# A604E.net
KiCad netlist of a schematic drawn in EAGLE
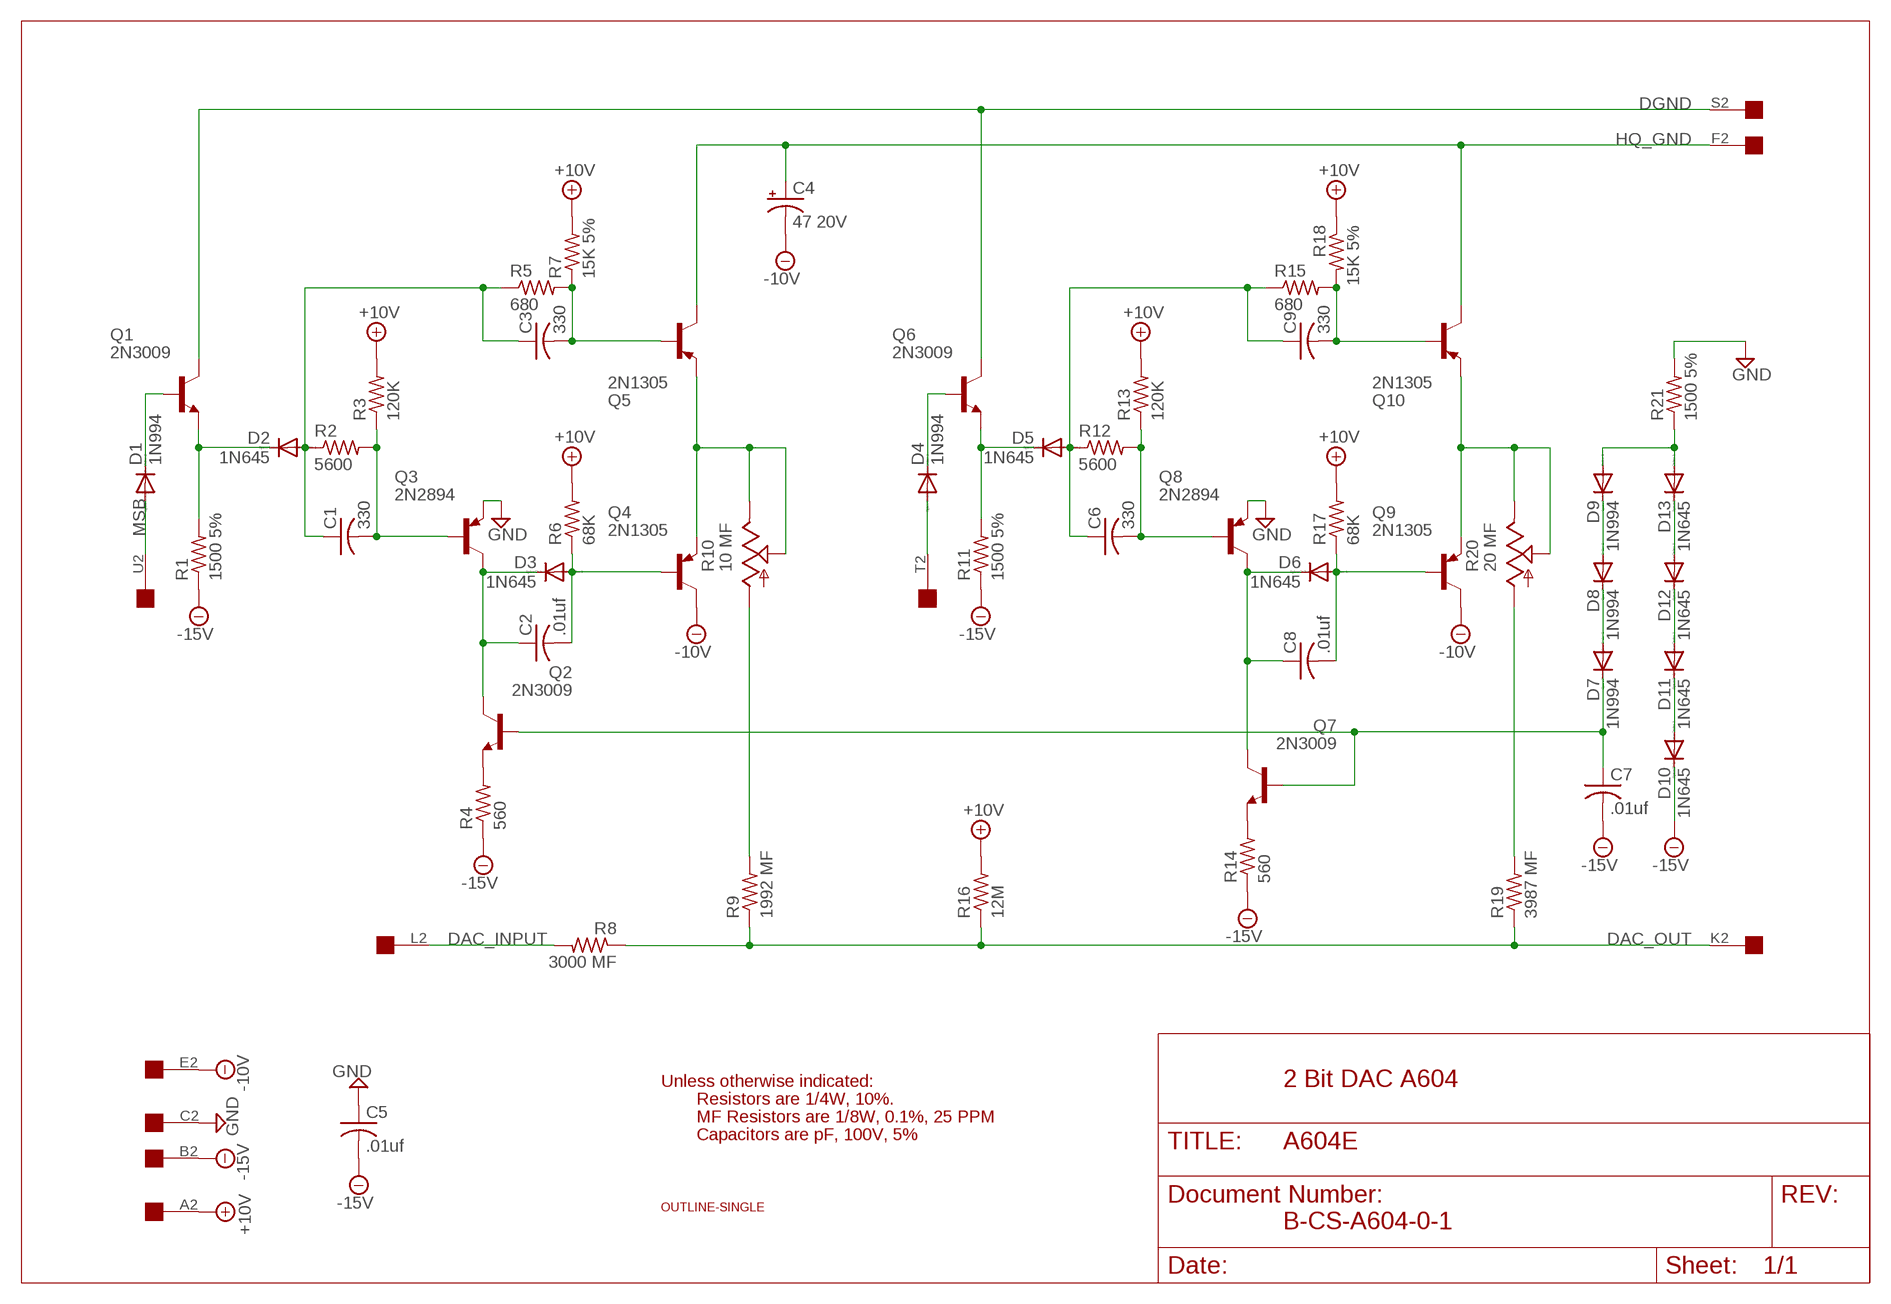
[diagram p0: schematic, sheet 1]

(export (version "E")
  (design (tool "Eeschema 10.0.6"))
  (components
    (comp (ref "C1")
      (value "330")
      (footprint "eagle-import:C075-032X103")
      (libsource (lib "eagle-import") (part "C-US075-032X103"))
    )
    (comp (ref "C2")
      (value ".01uf")
      (footprint "eagle-import:C050-025X075")
      (libsource (lib "eagle-import") (part "C-US050-025X075"))
    )
    (comp (ref "C3")
      (value "330")
      (footprint "eagle-import:C075-032X103")
      (libsource (lib "eagle-import") (part "C-US075-032X103"))
    )
    (comp (ref "C4")
      (value "47 20V")
      (footprint "eagle-import:E22-6")
      (libsource (lib "eagle-import") (part "CPOL-USE22-6AXIAL"))
    )
    (comp (ref "C5")
      (value ".01uf")
      (footprint "eagle-import:C050-025X075")
      (libsource (lib "eagle-import") (part "C-US050-025X075"))
    )
    (comp (ref "C6")
      (value "330")
      (footprint "eagle-import:C075-032X103")
      (libsource (lib "eagle-import") (part "C-US075-032X103"))
    )
    (comp (ref "C7")
      (value ".01uf")
      (footprint "eagle-import:C050-025X075")
      (libsource (lib "eagle-import") (part "C-US050-025X075"))
    )
    (comp (ref "C8")
      (value ".01uf")
      (footprint "eagle-import:C050-025X075")
      (libsource (lib "eagle-import") (part "C-US050-025X075"))
    )
    (comp (ref "C9")
      (value "330")
      (footprint "eagle-import:C075-032X103")
      (libsource (lib "eagle-import") (part "C-US075-032X103"))
    )
    (comp (ref "D1")
      (value "1N994")
      (footprint "eagle-import:DO35-10")
      (libsource (lib "eagle-import") (part "1N4148DO35-10"))
    )
    (comp (ref "D2")
      (value "1N645")
      (footprint "eagle-import:DO35-10")
      (libsource (lib "eagle-import") (part "1N4148DO35-10"))
    )
    (comp (ref "D3")
      (value "1N645")
      (footprint "eagle-import:DO35-10")
      (libsource (lib "eagle-import") (part "1N4148DO35-10"))
    )
    (comp (ref "D4")
      (value "1N994")
      (footprint "eagle-import:DO35-10")
      (libsource (lib "eagle-import") (part "1N4148DO35-10"))
    )
    (comp (ref "D5")
      (value "1N645")
      (footprint "eagle-import:DO35-10")
      (libsource (lib "eagle-import") (part "1N4148DO35-10"))
    )
    (comp (ref "D6")
      (value "1N645")
      (footprint "eagle-import:DO35-10")
      (libsource (lib "eagle-import") (part "1N4148DO35-10"))
    )
    (comp (ref "D7")
      (value "1N994")
      (footprint "eagle-import:DO35-10")
      (libsource (lib "eagle-import") (part "1N4148DO35-10"))
    )
    (comp (ref "D8")
      (value "1N994")
      (footprint "eagle-import:DO35-10")
      (libsource (lib "eagle-import") (part "1N4148DO35-10"))
    )
    (comp (ref "D9")
      (value "1N994")
      (footprint "eagle-import:DO35-10")
      (libsource (lib "eagle-import") (part "1N4148DO35-10"))
    )
    (comp (ref "D10")
      (value "1N645")
      (footprint "eagle-import:DO35-10")
      (libsource (lib "eagle-import") (part "1N4148DO35-10"))
    )
    (comp (ref "D11")
      (value "1N645")
      (footprint "eagle-import:DO35-10")
      (libsource (lib "eagle-import") (part "1N4148DO35-10"))
    )
    (comp (ref "D12")
      (value "1N645")
      (footprint "eagle-import:DO35-10")
      (libsource (lib "eagle-import") (part "1N4148DO35-10"))
    )
    (comp (ref "D13")
      (value "1N645")
      (footprint "eagle-import:DO35-10")
      (libsource (lib "eagle-import") (part "1N4148DO35-10"))
    )
    (comp (ref "Q1")
      (value "2N3009")
      (footprint "eagle-import:TO39")
      (libsource (lib "eagle-import") (part "-NPN-TO39-EBC2N1613"))
    )
    (comp (ref "Q2")
      (value "2N3009")
      (footprint "eagle-import:TO39")
      (libsource (lib "eagle-import") (part "-NPN-TO39-EBC2N1613"))
    )
    (comp (ref "Q3")
      (value "2N2894")
      (footprint "eagle-import:TO39")
      (libsource (lib "eagle-import") (part "2N2904A"))
    )
    (comp (ref "Q4")
      (value "2N1305")
      (footprint "eagle-import:TO39")
      (libsource (lib "eagle-import") (part "2N2904A"))
    )
    (comp (ref "Q5")
      (value "2N1305")
      (footprint "eagle-import:TO39")
      (libsource (lib "eagle-import") (part "2N2904A"))
    )
    (comp (ref "Q6")
      (value "2N3009")
      (footprint "eagle-import:TO39")
      (libsource (lib "eagle-import") (part "-NPN-TO39-EBC2N1613"))
    )
    (comp (ref "Q7")
      (value "2N3009")
      (footprint "eagle-import:TO39")
      (libsource (lib "eagle-import") (part "-NPN-TO39-EBC2N1613"))
    )
    (comp (ref "Q8")
      (value "2N2894")
      (footprint "eagle-import:TO39")
      (libsource (lib "eagle-import") (part "2N2904A"))
    )
    (comp (ref "Q9")
      (value "2N1305")
      (footprint "eagle-import:TO39")
      (libsource (lib "eagle-import") (part "2N2904A"))
    )
    (comp (ref "Q10")
      (value "2N1305")
      (footprint "eagle-import:TO39")
      (libsource (lib "eagle-import") (part "2N2904A"))
    )
    (comp (ref "R1")
      (value "1500 5%")
      (footprint "eagle-import:0207_10")
      (libsource (lib "eagle-import") (part "R-US_0207/10"))
    )
    (comp (ref "R2")
      (value "5600")
      (footprint "eagle-import:0207_10")
      (libsource (lib "eagle-import") (part "R-US_0207/10"))
    )
    (comp (ref "R3")
      (value "120K")
      (footprint "eagle-import:0207_10")
      (libsource (lib "eagle-import") (part "R-US_0207/10"))
    )
    (comp (ref "R4")
      (value "560")
      (footprint "eagle-import:0207_10")
      (libsource (lib "eagle-import") (part "R-US_0207/10"))
    )
    (comp (ref "R5")
      (value "680")
      (footprint "eagle-import:0207_10")
      (libsource (lib "eagle-import") (part "R-US_0207/10"))
    )
    (comp (ref "R6")
      (value "68K")
      (footprint "eagle-import:0207_10")
      (libsource (lib "eagle-import") (part "R-US_0207/10"))
    )
    (comp (ref "R7")
      (value "15K 5%")
      (footprint "eagle-import:0207_10")
      (libsource (lib "eagle-import") (part "R-US_0207/10"))
    )
    (comp (ref "R8")
      (value "3000 MF")
      (footprint "eagle-import:0309_12")
      (libsource (lib "eagle-import") (part "R-US_0309/12"))
    )
    (comp (ref "R9")
      (value "1992 MF")
      (footprint "eagle-import:0309_12")
      (libsource (lib "eagle-import") (part "R-US_0309/12"))
    )
    (comp (ref "R10")
      (value "10 MF")
      (footprint "eagle-import:S75P")
      (libsource (lib "eagle-import") (part "TRIM_US-S75P"))
    )
    (comp (ref "R11")
      (value "1500 5%")
      (footprint "eagle-import:0207_10")
      (libsource (lib "eagle-import") (part "R-US_0207/10"))
    )
    (comp (ref "R12")
      (value "5600")
      (footprint "eagle-import:0207_10")
      (libsource (lib "eagle-import") (part "R-US_0207/10"))
    )
    (comp (ref "R13")
      (value "120K")
      (footprint "eagle-import:0207_10")
      (libsource (lib "eagle-import") (part "R-US_0207/10"))
    )
    (comp (ref "R14")
      (value "560")
      (footprint "eagle-import:0207_10")
      (libsource (lib "eagle-import") (part "R-US_0207/10"))
    )
    (comp (ref "R15")
      (value "680")
      (footprint "eagle-import:0207_10")
      (libsource (lib "eagle-import") (part "R-US_0207/10"))
    )
    (comp (ref "R16")
      (value "12M")
      (footprint "eagle-import:0207_10")
      (libsource (lib "eagle-import") (part "R-US_0207/10"))
    )
    (comp (ref "R17")
      (value "68K")
      (footprint "eagle-import:0207_10")
      (libsource (lib "eagle-import") (part "R-US_0207/10"))
    )
    (comp (ref "R18")
      (value "15K 5%")
      (footprint "eagle-import:0207_10")
      (libsource (lib "eagle-import") (part "R-US_0207/10"))
    )
    (comp (ref "R19")
      (value "3987 MF")
      (footprint "eagle-import:0309_12")
      (libsource (lib "eagle-import") (part "R-US_0309/12"))
    )
    (comp (ref "R20")
      (value "20 MF")
      (footprint "eagle-import:S75P")
      (libsource (lib "eagle-import") (part "TRIM_US-S75P"))
    )
    (comp (ref "R21")
      (value "1500 5%")
      (footprint "eagle-import:0207_10")
      (libsource (lib "eagle-import") (part "R-US_0207/10"))
    )
    (comp (ref "U$1")
      (value "OUTLINE-SINGLE")
      (footprint "eagle-import:SINGLE")
      (libsource (lib "eagle-import") (part "OUTLINE-SINGLE"))
    )
    (comp (ref "U$3")
      (value "EDGE-1")
      (footprint "eagle-import:EDGE-CON1")
      (libsource (lib "eagle-import") (part "EDGE-1"))
    )
  )
  (nets
    (net (code "1") (name "+10V") (class "Default")
      (node (ref "R13") (pin "2") (pinfunction "2_2") (pintype "passive"))
      (node (ref "R16") (pin "2") (pinfunction "2_2") (pintype "passive"))
      (node (ref "R17") (pin "2") (pinfunction "2_2") (pintype "passive"))
      (node (ref "R18") (pin "1") (pinfunction "1_1") (pintype "passive"))
      (node (ref "R3") (pin "2") (pinfunction "2_2") (pintype "passive"))
      (node (ref "R6") (pin "2") (pinfunction "2_2") (pintype "passive"))
      (node (ref "R7") (pin "2") (pinfunction "2_2") (pintype "passive"))
      (node (ref "U$3") (pin "A2") (pinfunction "1_A2") (pintype "bidirectional"))
    )
    (net (code "2") (name "-10V") (class "Default")
      (node (ref "C4") (pin "-") (pinfunction "-_-") (pintype "passive"))
      (node (ref "Q4") (pin "3") (pinfunction "C_3") (pintype "passive"))
      (node (ref "Q9") (pin "3") (pinfunction "C_3") (pintype "passive"))
      (node (ref "U$3") (pin "E2") (pinfunction "1_E2") (pintype "bidirectional"))
    )
    (net (code "3") (name "-15V") (class "Default")
      (node (ref "C5") (pin "2") (pinfunction "2_2") (pintype "passive"))
      (node (ref "C7") (pin "2") (pinfunction "2_2") (pintype "passive"))
      (node (ref "D10") (pin "C") (pinfunction "C_C") (pintype "passive"))
      (node (ref "R1") (pin "1") (pinfunction "1_1") (pintype "passive"))
      (node (ref "R11") (pin "1") (pinfunction "1_1") (pintype "passive"))
      (node (ref "R14") (pin "1") (pinfunction "1_1") (pintype "passive"))
      (node (ref "R4") (pin "1") (pinfunction "1_1") (pintype "passive"))
      (node (ref "U$3") (pin "B2") (pinfunction "1_B2") (pintype "bidirectional"))
    )
    (net (code "4") (name "/DAC_INPUT") (class "Default")
      (node (ref "R8") (pin "2") (pinfunction "2_2") (pintype "passive"))
      (node (ref "U$3") (pin "L2") (pinfunction "1_L2") (pintype "bidirectional"))
    )
    (net (code "5") (name "/DAC_OUT") (class "Default")
      (node (ref "R16") (pin "1") (pinfunction "1_1") (pintype "passive"))
      (node (ref "R19") (pin "1") (pinfunction "1_1") (pintype "passive"))
      (node (ref "R8") (pin "1") (pinfunction "1_1") (pintype "passive"))
      (node (ref "R9") (pin "1") (pinfunction "1_1") (pintype "passive"))
      (node (ref "U$3") (pin "K2") (pinfunction "1_K2") (pintype "bidirectional"))
    )
    (net (code "6") (name "/DGND") (class "Default")
      (node (ref "Q1") (pin "3") (pinfunction "C_3") (pintype "passive"))
      (node (ref "Q6") (pin "3") (pinfunction "C_3") (pintype "passive"))
      (node (ref "U$3") (pin "S2") (pinfunction "1_S2") (pintype "bidirectional"))
    )
    (net (code "7") (name "/HQ_GND") (class "Default")
      (node (ref "C4") (pin "+") (pinfunction "+_+") (pintype "passive"))
      (node (ref "Q10") (pin "3") (pinfunction "C_3") (pintype "passive"))
      (node (ref "Q5") (pin "3") (pinfunction "C_3") (pintype "passive"))
      (node (ref "U$3") (pin "F2") (pinfunction "1_F2") (pintype "bidirectional"))
    )
    (net (code "8") (name "/MSB") (class "Default")
      (node (ref "D1") (pin "A") (pinfunction "A_A") (pintype "passive"))
      (node (ref "U$3") (pin "U2") (pinfunction "1_U2") (pintype "bidirectional"))
    )
    (net (code "9") (name "GND") (class "Default")
      (node (ref "C5") (pin "1") (pinfunction "1_1") (pintype "passive"))
      (node (ref "Q3") (pin "1") (pinfunction "E_1") (pintype "passive"))
      (node (ref "Q8") (pin "1") (pinfunction "E_1") (pintype "passive"))
      (node (ref "R21") (pin "2") (pinfunction "2_2") (pintype "passive"))
      (node (ref "U$3") (pin "C2") (pinfunction "1_C2") (pintype "bidirectional"))
    )
    (net (code "10") (name "Net-(C1-Pad1)") (class "Default")
      (node (ref "C1") (pin "1") (pinfunction "1_1") (pintype "passive"))
      (node (ref "C3") (pin "1") (pinfunction "1_1") (pintype "passive"))
      (node (ref "D2") (pin "A") (pinfunction "A_A") (pintype "passive"))
      (node (ref "R2") (pin "1") (pinfunction "1_1") (pintype "passive"))
      (node (ref "R5") (pin "1") (pinfunction "1_1") (pintype "passive"))
    )
    (net (code "11") (name "Net-(C6-Pad1)") (class "Default")
      (node (ref "C6") (pin "1") (pinfunction "1_1") (pintype "passive"))
      (node (ref "C9") (pin "1") (pinfunction "1_1") (pintype "passive"))
      (node (ref "D5") (pin "A") (pinfunction "A_A") (pintype "passive"))
      (node (ref "R12") (pin "1") (pinfunction "1_1") (pintype "passive"))
      (node (ref "R15") (pin "1") (pinfunction "1_1") (pintype "passive"))
    )
    (net (code "12") (name "Net-(D7-PadA)") (class "Default")
      (node (ref "D7") (pin "A") (pinfunction "A_A") (pintype "passive"))
      (node (ref "D8") (pin "C") (pinfunction "C_C") (pintype "passive"))
    )
    (net (code "13") (name "Net-(D8-PadA)") (class "Default")
      (node (ref "D8") (pin "A") (pinfunction "A_A") (pintype "passive"))
      (node (ref "D9") (pin "C") (pinfunction "C_C") (pintype "passive"))
    )
    (net (code "14") (name "Net-(D10-PadA)") (class "Default")
      (node (ref "D10") (pin "A") (pinfunction "A_A") (pintype "passive"))
      (node (ref "D11") (pin "C") (pinfunction "C_C") (pintype "passive"))
    )
    (net (code "15") (name "Net-(D11-PadA)") (class "Default")
      (node (ref "D11") (pin "A") (pinfunction "A_A") (pintype "passive"))
      (node (ref "D12") (pin "C") (pinfunction "C_C") (pintype "passive"))
    )
    (net (code "16") (name "Net-(D12-PadA)") (class "Default")
      (node (ref "D12") (pin "A") (pinfunction "A_A") (pintype "passive"))
      (node (ref "D13") (pin "C") (pinfunction "C_C") (pintype "passive"))
    )
    (net (code "17") (name "Net-(D13-PadA)") (class "Default")
      (node (ref "D13") (pin "A") (pinfunction "A_A") (pintype "passive"))
      (node (ref "D9") (pin "A") (pinfunction "A_A") (pintype "passive"))
      (node (ref "R21") (pin "1") (pinfunction "1_1") (pintype "passive"))
    )
    (net (code "18") (name "Net-(Q1-B)") (class "Default")
      (node (ref "D1") (pin "C") (pinfunction "C_C") (pintype "passive"))
      (node (ref "Q1") (pin "2") (pinfunction "B_2") (pintype "passive"))
    )
    (net (code "19") (name "Net-(Q1-E)") (class "Default")
      (node (ref "D2") (pin "C") (pinfunction "C_C") (pintype "passive"))
      (node (ref "Q1") (pin "1") (pinfunction "E_1") (pintype "passive"))
      (node (ref "R1") (pin "2") (pinfunction "2_2") (pintype "passive"))
    )
    (net (code "20") (name "Net-(Q2-B)") (class "Default")
      (node (ref "C7") (pin "1") (pinfunction "1_1") (pintype "passive"))
      (node (ref "D7") (pin "C") (pinfunction "C_C") (pintype "passive"))
      (node (ref "Q2") (pin "2") (pinfunction "B_2") (pintype "passive"))
      (node (ref "Q7") (pin "2") (pinfunction "B_2") (pintype "passive"))
    )
    (net (code "21") (name "Net-(Q2-C)") (class "Default")
      (node (ref "C2") (pin "1") (pinfunction "1_1") (pintype "passive"))
      (node (ref "D3") (pin "C") (pinfunction "C_C") (pintype "passive"))
      (node (ref "Q2") (pin "3") (pinfunction "C_3") (pintype "passive"))
      (node (ref "Q3") (pin "3") (pinfunction "C_3") (pintype "passive"))
    )
    (net (code "22") (name "Net-(Q2-E)") (class "Default")
      (node (ref "Q2") (pin "1") (pinfunction "E_1") (pintype "passive"))
      (node (ref "R4") (pin "2") (pinfunction "2_2") (pintype "passive"))
    )
    (net (code "23") (name "Net-(Q3-B)") (class "Default")
      (node (ref "C1") (pin "2") (pinfunction "2_2") (pintype "passive"))
      (node (ref "Q3") (pin "2") (pinfunction "B_2") (pintype "passive"))
      (node (ref "R2") (pin "2") (pinfunction "2_2") (pintype "passive"))
      (node (ref "R3") (pin "1") (pinfunction "1_1") (pintype "passive"))
    )
    (net (code "24") (name "Net-(Q4-B)") (class "Default")
      (node (ref "C2") (pin "2") (pinfunction "2_2") (pintype "passive"))
      (node (ref "D3") (pin "A") (pinfunction "A_A") (pintype "passive"))
      (node (ref "Q4") (pin "2") (pinfunction "B_2") (pintype "passive"))
      (node (ref "R6") (pin "1") (pinfunction "1_1") (pintype "passive"))
    )
    (net (code "25") (name "Net-(Q4-E)") (class "Default")
      (node (ref "Q4") (pin "1") (pinfunction "E_1") (pintype "passive"))
      (node (ref "Q5") (pin "1") (pinfunction "E_1") (pintype "passive"))
      (node (ref "R10") (pin "E") (pinfunction "E_E") (pintype "passive"))
      (node (ref "R10") (pin "S") (pinfunction "S_S") (pintype "passive"))
    )
    (net (code "26") (name "Net-(Q5-B)") (class "Default")
      (node (ref "C3") (pin "2") (pinfunction "2_2") (pintype "passive"))
      (node (ref "Q5") (pin "2") (pinfunction "B_2") (pintype "passive"))
      (node (ref "R5") (pin "2") (pinfunction "2_2") (pintype "passive"))
      (node (ref "R7") (pin "1") (pinfunction "1_1") (pintype "passive"))
    )
    (net (code "27") (name "Net-(Q6-B)") (class "Default")
      (node (ref "D4") (pin "C") (pinfunction "C_C") (pintype "passive"))
      (node (ref "Q6") (pin "2") (pinfunction "B_2") (pintype "passive"))
    )
    (net (code "28") (name "Net-(Q6-E)") (class "Default")
      (node (ref "D5") (pin "C") (pinfunction "C_C") (pintype "passive"))
      (node (ref "Q6") (pin "1") (pinfunction "E_1") (pintype "passive"))
      (node (ref "R11") (pin "2") (pinfunction "2_2") (pintype "passive"))
    )
    (net (code "29") (name "Net-(Q7-C)") (class "Default")
      (node (ref "C8") (pin "1") (pinfunction "1_1") (pintype "passive"))
      (node (ref "D6") (pin "C") (pinfunction "C_C") (pintype "passive"))
      (node (ref "Q7") (pin "3") (pinfunction "C_3") (pintype "passive"))
      (node (ref "Q8") (pin "3") (pinfunction "C_3") (pintype "passive"))
    )
    (net (code "30") (name "Net-(Q7-E)") (class "Default")
      (node (ref "Q7") (pin "1") (pinfunction "E_1") (pintype "passive"))
      (node (ref "R14") (pin "2") (pinfunction "2_2") (pintype "passive"))
    )
    (net (code "31") (name "Net-(Q8-B)") (class "Default")
      (node (ref "C6") (pin "2") (pinfunction "2_2") (pintype "passive"))
      (node (ref "Q8") (pin "2") (pinfunction "B_2") (pintype "passive"))
      (node (ref "R12") (pin "2") (pinfunction "2_2") (pintype "passive"))
      (node (ref "R13") (pin "1") (pinfunction "1_1") (pintype "passive"))
    )
    (net (code "32") (name "Net-(Q9-B)") (class "Default")
      (node (ref "C8") (pin "2") (pinfunction "2_2") (pintype "passive"))
      (node (ref "D6") (pin "A") (pinfunction "A_A") (pintype "passive"))
      (node (ref "Q9") (pin "2") (pinfunction "B_2") (pintype "passive"))
      (node (ref "R17") (pin "1") (pinfunction "1_1") (pintype "passive"))
    )
    (net (code "33") (name "Net-(Q10-B)") (class "Default")
      (node (ref "C9") (pin "2") (pinfunction "2_2") (pintype "passive"))
      (node (ref "Q10") (pin "2") (pinfunction "B_2") (pintype "passive"))
      (node (ref "R15") (pin "2") (pinfunction "2_2") (pintype "passive"))
      (node (ref "R18") (pin "2") (pinfunction "2_2") (pintype "passive"))
    )
    (net (code "34") (name "Net-(Q10-E)") (class "Default")
      (node (ref "Q10") (pin "1") (pinfunction "E_1") (pintype "passive"))
      (node (ref "Q9") (pin "1") (pinfunction "E_1") (pintype "passive"))
      (node (ref "R20") (pin "E") (pinfunction "E_E") (pintype "passive"))
      (node (ref "R20") (pin "S") (pinfunction "S_S") (pintype "passive"))
    )
    (net (code "35") (name "Net-(R10-PadA)") (class "Default")
      (node (ref "R10") (pin "A") (pinfunction "A_A") (pintype "passive"))
      (node (ref "R9") (pin "2") (pinfunction "2_2") (pintype "passive"))
    )
    (net (code "36") (name "Net-(R19-Pad2)") (class "Default")
      (node (ref "R19") (pin "2") (pinfunction "2_2") (pintype "passive"))
      (node (ref "R20") (pin "A") (pinfunction "A_A") (pintype "passive"))
    )
    (net (code "37") (name "Net-(U$3P-1)") (class "Default")
      (node (ref "D4") (pin "A") (pinfunction "A_A") (pintype "passive"))
      (node (ref "U$3") (pin "T2") (pinfunction "1_T2") (pintype "bidirectional"))
    )
  )
)
